# TLV70433.net
KiCad netlist of a schematic drawn in EAGLE
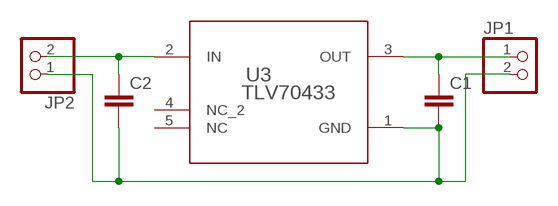
[diagram p0: schematic, sheet 1]

(export (version "E")
  (design (tool "Eeschema 10.0.6"))
  (components
    (comp (ref "C1")
      (value "C-EUC1206")
      (footprint "eagle-import:C1206")
      (libsource (lib "eagle-import") (part "C-EUC1206"))
    )
    (comp (ref "C2")
      (value "C-EUC1206")
      (footprint "eagle-import:C1206")
      (libsource (lib "eagle-import") (part "C-EUC1206"))
    )
    (comp (ref "JP1")
      (value "PINHD-1X2")
      (footprint "eagle-import:1X02")
      (libsource (lib "eagle-import") (part "PINHD-1X2"))
    )
    (comp (ref "JP2")
      (value "PINHD-1X2")
      (footprint "eagle-import:1X02")
      (libsource (lib "eagle-import") (part "PINHD-1X2"))
    )
    (comp (ref "U3")
      (value "TLV70433")
      (footprint "eagle-import:DBV0005A_N")
      (fields (field (name "MANUFACTURER") "Texas Instruments") (field (name "PARTNUMBER") "TLV70430DBVR"))
      (libsource (lib "eagle-import") (part "TLV70430DBVR"))
    )
  )
  (nets
    (net (code "1") (name "Net-(U3-GND)") (class "Default")
      (node (ref "C1") (pin "2") (pinfunction "2_2") (pintype "passive"))
      (node (ref "C2") (pin "2") (pinfunction "2_2") (pintype "passive"))
      (node (ref "JP1") (pin "2") (pinfunction "2_2") (pintype "passive"))
      (node (ref "JP2") (pin "1") (pinfunction "1_1") (pintype "passive"))
      (node (ref "U3") (pin "1") (pinfunction "GND_1") (pintype "power_in"))
    )
    (net (code "2") (name "Net-(U3-IN)") (class "Default")
      (node (ref "C2") (pin "1") (pinfunction "1_1") (pintype "passive"))
      (node (ref "JP2") (pin "2") (pinfunction "2_2") (pintype "passive"))
      (node (ref "U3") (pin "2") (pinfunction "IN_2") (pintype "power_in"))
    )
    (net (code "3") (name "Net-(U3-OUT)") (class "Default")
      (node (ref "C1") (pin "1") (pinfunction "1_1") (pintype "passive"))
      (node (ref "JP1") (pin "1") (pinfunction "1_1") (pintype "passive"))
      (node (ref "U3") (pin "3") (pinfunction "OUT_3") (pintype "power_in"))
    )
    (net (code "4") (name "unconnected-(U3-NC-Pad5)") (class "Default")
      (node (ref "U3") (pin "5") (pinfunction "NC_5") (pintype "passive"))
    )
    (net (code "5") (name "unconnected-(U3-NC_2-Pad4)") (class "Default")
      (node (ref "U3") (pin "4") (pinfunction "NC_2_4") (pintype "passive"))
    )
  )
)
